# Breakoutboard.net
KiCad netlist of a schematic drawn in EAGLE
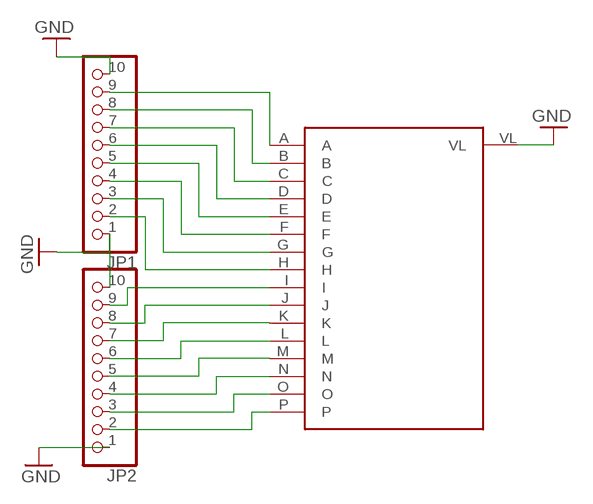
[diagram p0: schematic, sheet 1]

(export (version "E")
  (design (tool "Eeschema 10.0.6"))
  (components
    (comp (ref "JP1")
      (value "PINHD-1X10")
      (footprint "eagle-import:1X10")
      (libsource (lib "eagle-import") (part "PINHD-1X10"))
    )
    (comp (ref "JP2")
      (value "PINHD-1X10")
      (footprint "eagle-import:1X10")
      (libsource (lib "eagle-import") (part "PINHD-1X10"))
    )
    (comp (ref "U$1")
      (value "1.27KW-104AL")
      (footprint "eagle-import:127")
      (libsource (lib "eagle-import") (part "1.27KW-104AL"))
    )
  )
  (nets
    (net (code "1") (name "GND") (class "Default")
      (node (ref "JP1") (pin "1") (pinfunction "1_1") (pintype "passive"))
      (node (ref "JP1") (pin "10") (pinfunction "10_10") (pintype "passive"))
      (node (ref "JP2") (pin "1") (pinfunction "1_1") (pintype "passive"))
      (node (ref "JP2") (pin "10") (pinfunction "10_10") (pintype "passive"))
      (node (ref "U$1") (pin "VL") (pinfunction "VL_VL") (pintype "bidirectional"))
    )
    (net (code "2") (name "Net-(JP1-Pad2)") (class "Default")
      (node (ref "JP1") (pin "2") (pinfunction "2_2") (pintype "passive"))
      (node (ref "U$1") (pin "H") (pinfunction "H_H") (pintype "bidirectional"))
    )
    (net (code "3") (name "Net-(JP1-Pad3)") (class "Default")
      (node (ref "JP1") (pin "3") (pinfunction "3_3") (pintype "passive"))
      (node (ref "U$1") (pin "G") (pinfunction "G_G") (pintype "bidirectional"))
    )
    (net (code "4") (name "Net-(JP1-Pad4)") (class "Default")
      (node (ref "JP1") (pin "4") (pinfunction "4_4") (pintype "passive"))
      (node (ref "U$1") (pin "F") (pinfunction "F_F") (pintype "bidirectional"))
    )
    (net (code "5") (name "Net-(JP1-Pad5)") (class "Default")
      (node (ref "JP1") (pin "5") (pinfunction "5_5") (pintype "passive"))
      (node (ref "U$1") (pin "E") (pinfunction "E_E") (pintype "bidirectional"))
    )
    (net (code "6") (name "Net-(JP1-Pad6)") (class "Default")
      (node (ref "JP1") (pin "6") (pinfunction "6_6") (pintype "passive"))
      (node (ref "U$1") (pin "D") (pinfunction "D_D") (pintype "bidirectional"))
    )
    (net (code "7") (name "Net-(JP1-Pad7)") (class "Default")
      (node (ref "JP1") (pin "7") (pinfunction "7_7") (pintype "passive"))
      (node (ref "U$1") (pin "C") (pinfunction "C_C") (pintype "bidirectional"))
    )
    (net (code "8") (name "Net-(JP1-Pad8)") (class "Default")
      (node (ref "JP1") (pin "8") (pinfunction "8_8") (pintype "passive"))
      (node (ref "U$1") (pin "B") (pinfunction "B_B") (pintype "bidirectional"))
    )
    (net (code "9") (name "Net-(JP1-Pad9)") (class "Default")
      (node (ref "JP1") (pin "9") (pinfunction "9_9") (pintype "passive"))
      (node (ref "U$1") (pin "A") (pinfunction "A_A") (pintype "bidirectional"))
    )
    (net (code "10") (name "Net-(JP2-Pad2)") (class "Default")
      (node (ref "JP2") (pin "2") (pinfunction "2_2") (pintype "passive"))
      (node (ref "U$1") (pin "P") (pinfunction "P_P") (pintype "bidirectional"))
    )
    (net (code "11") (name "Net-(JP2-Pad3)") (class "Default")
      (node (ref "JP2") (pin "3") (pinfunction "3_3") (pintype "passive"))
      (node (ref "U$1") (pin "O") (pinfunction "O_O") (pintype "bidirectional"))
    )
    (net (code "12") (name "Net-(JP2-Pad4)") (class "Default")
      (node (ref "JP2") (pin "4") (pinfunction "4_4") (pintype "passive"))
      (node (ref "U$1") (pin "N") (pinfunction "N_N") (pintype "bidirectional"))
    )
    (net (code "13") (name "Net-(JP2-Pad5)") (class "Default")
      (node (ref "JP2") (pin "5") (pinfunction "5_5") (pintype "passive"))
      (node (ref "U$1") (pin "M") (pinfunction "M_M") (pintype "bidirectional"))
    )
    (net (code "14") (name "Net-(JP2-Pad6)") (class "Default")
      (node (ref "JP2") (pin "6") (pinfunction "6_6") (pintype "passive"))
      (node (ref "U$1") (pin "L") (pinfunction "L_L") (pintype "bidirectional"))
    )
    (net (code "15") (name "Net-(JP2-Pad7)") (class "Default")
      (node (ref "JP2") (pin "7") (pinfunction "7_7") (pintype "passive"))
      (node (ref "U$1") (pin "K") (pinfunction "K_K") (pintype "bidirectional"))
    )
    (net (code "16") (name "Net-(JP2-Pad8)") (class "Default")
      (node (ref "JP2") (pin "8") (pinfunction "8_8") (pintype "passive"))
      (node (ref "U$1") (pin "J") (pinfunction "J_J") (pintype "bidirectional"))
    )
    (net (code "17") (name "Net-(JP2-Pad9)") (class "Default")
      (node (ref "JP2") (pin "9") (pinfunction "9_9") (pintype "passive"))
      (node (ref "U$1") (pin "I") (pinfunction "I_I") (pintype "bidirectional"))
    )
  )
)
